# ESC.net
KiCad netlist of a schematic drawn in Altium Designer
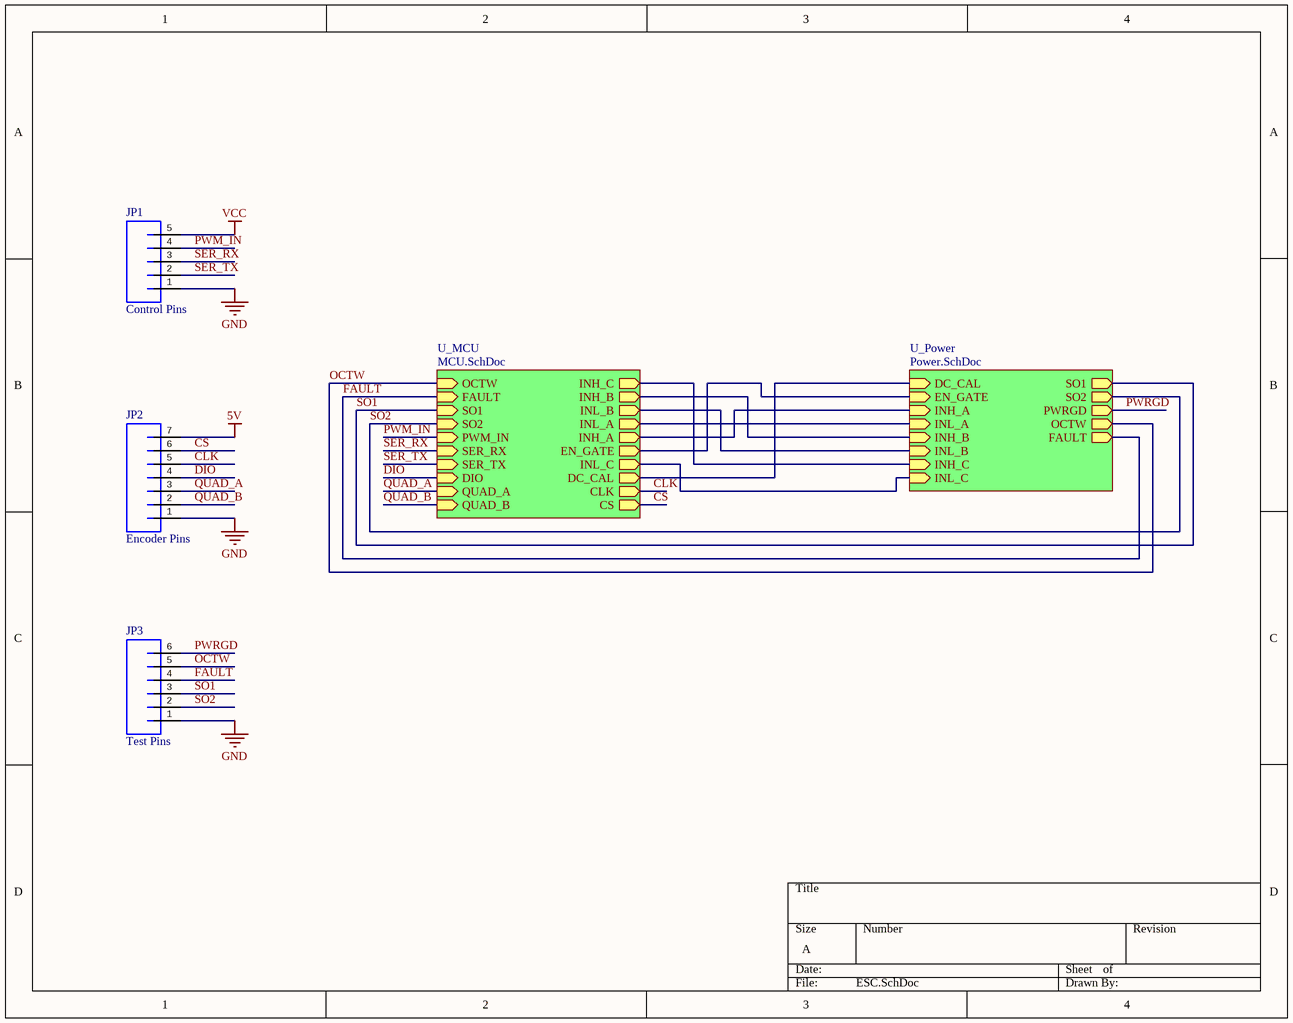
[diagram p0: ESC.SchDoc]

(export (version "E")
  (design (tool "Eeschema 10.0.6"))
  (components
    (comp (ref "JP1")
      (value "Control Pins")
      (footprint "JST-5-PTH-VERT")
      (libsource (lib "Components") (part "JST_5_VERT"))
    )
    (comp (ref "JP2")
      (value "Encoder Pins")
      (footprint "JST-7-PTH-VERT")
      (libsource (lib "Components") (part "JST_7_VERT"))
    )
    (comp (ref "JP3")
      (value "Test Pins")
      (footprint "JST-6-PTH-VERT")
      (libsource (lib "Components") (part "JST_6_VERT"))
    )
  )
  (nets
    (net (code "1") (name "/CLK") (class "Default")
      (node (ref "JP2") (pin "5") (pinfunction "5_5") (pintype "passive"))
    )
    (net (code "2") (name "/CS") (class "Default")
      (node (ref "JP2") (pin "6") (pinfunction "6_6") (pintype "passive"))
    )
    (net (code "4") (name "/DIO") (class "Default")
      (node (ref "JP2") (pin "4") (pinfunction "4_4") (pintype "passive"))
    )
    (net (code "6") (name "/FAULT") (class "Default")
      (node (ref "JP3") (pin "4") (pinfunction "4_4") (pintype "passive"))
    )
    (net (code "13") (name "/OCTW") (class "Default")
      (node (ref "JP3") (pin "5") (pinfunction "5_5") (pintype "passive"))
    )
    (net (code "14") (name "/PWM_IN") (class "Default")
      (node (ref "JP1") (pin "4") (pinfunction "4_4") (pintype "passive"))
    )
    (net (code "15") (name "/PWRGD") (class "Default")
      (node (ref "JP3") (pin "6") (pinfunction "6_6") (pintype "passive"))
    )
    (net (code "16") (name "/QUAD_A") (class "Default")
      (node (ref "JP2") (pin "3") (pinfunction "3_3") (pintype "passive"))
    )
    (net (code "17") (name "/QUAD_B") (class "Default")
      (node (ref "JP2") (pin "2") (pinfunction "2_2") (pintype "passive"))
    )
    (net (code "18") (name "/SER_RX") (class "Default")
      (node (ref "JP1") (pin "3") (pinfunction "3_3") (pintype "passive"))
    )
    (net (code "19") (name "/SER_TX") (class "Default")
      (node (ref "JP1") (pin "2") (pinfunction "2_2") (pintype "passive"))
    )
    (net (code "20") (name "/SO1") (class "Default")
      (node (ref "JP3") (pin "3") (pinfunction "3_3") (pintype "passive"))
    )
    (net (code "21") (name "/SO2") (class "Default")
      (node (ref "JP3") (pin "2") (pinfunction "2_2") (pintype "passive"))
    )
    (net (code "22") (name "5V") (class "Default")
      (node (ref "JP2") (pin "7") (pinfunction "7_7") (pintype "passive"))
    )
    (net (code "23") (name "GND") (class "Default")
      (node (ref "JP1") (pin "1") (pinfunction "1_1") (pintype "passive"))
      (node (ref "JP2") (pin "1") (pinfunction "1_1") (pintype "passive"))
      (node (ref "JP3") (pin "1") (pinfunction "1_1") (pintype "passive"))
    )
    (net (code "24") (name "VCC") (class "Default")
      (node (ref "JP1") (pin "5") (pinfunction "5_5") (pintype "passive"))
    )
  )
)
